# design.net
KiCad netlist of a schematic drawn in Altium Designer
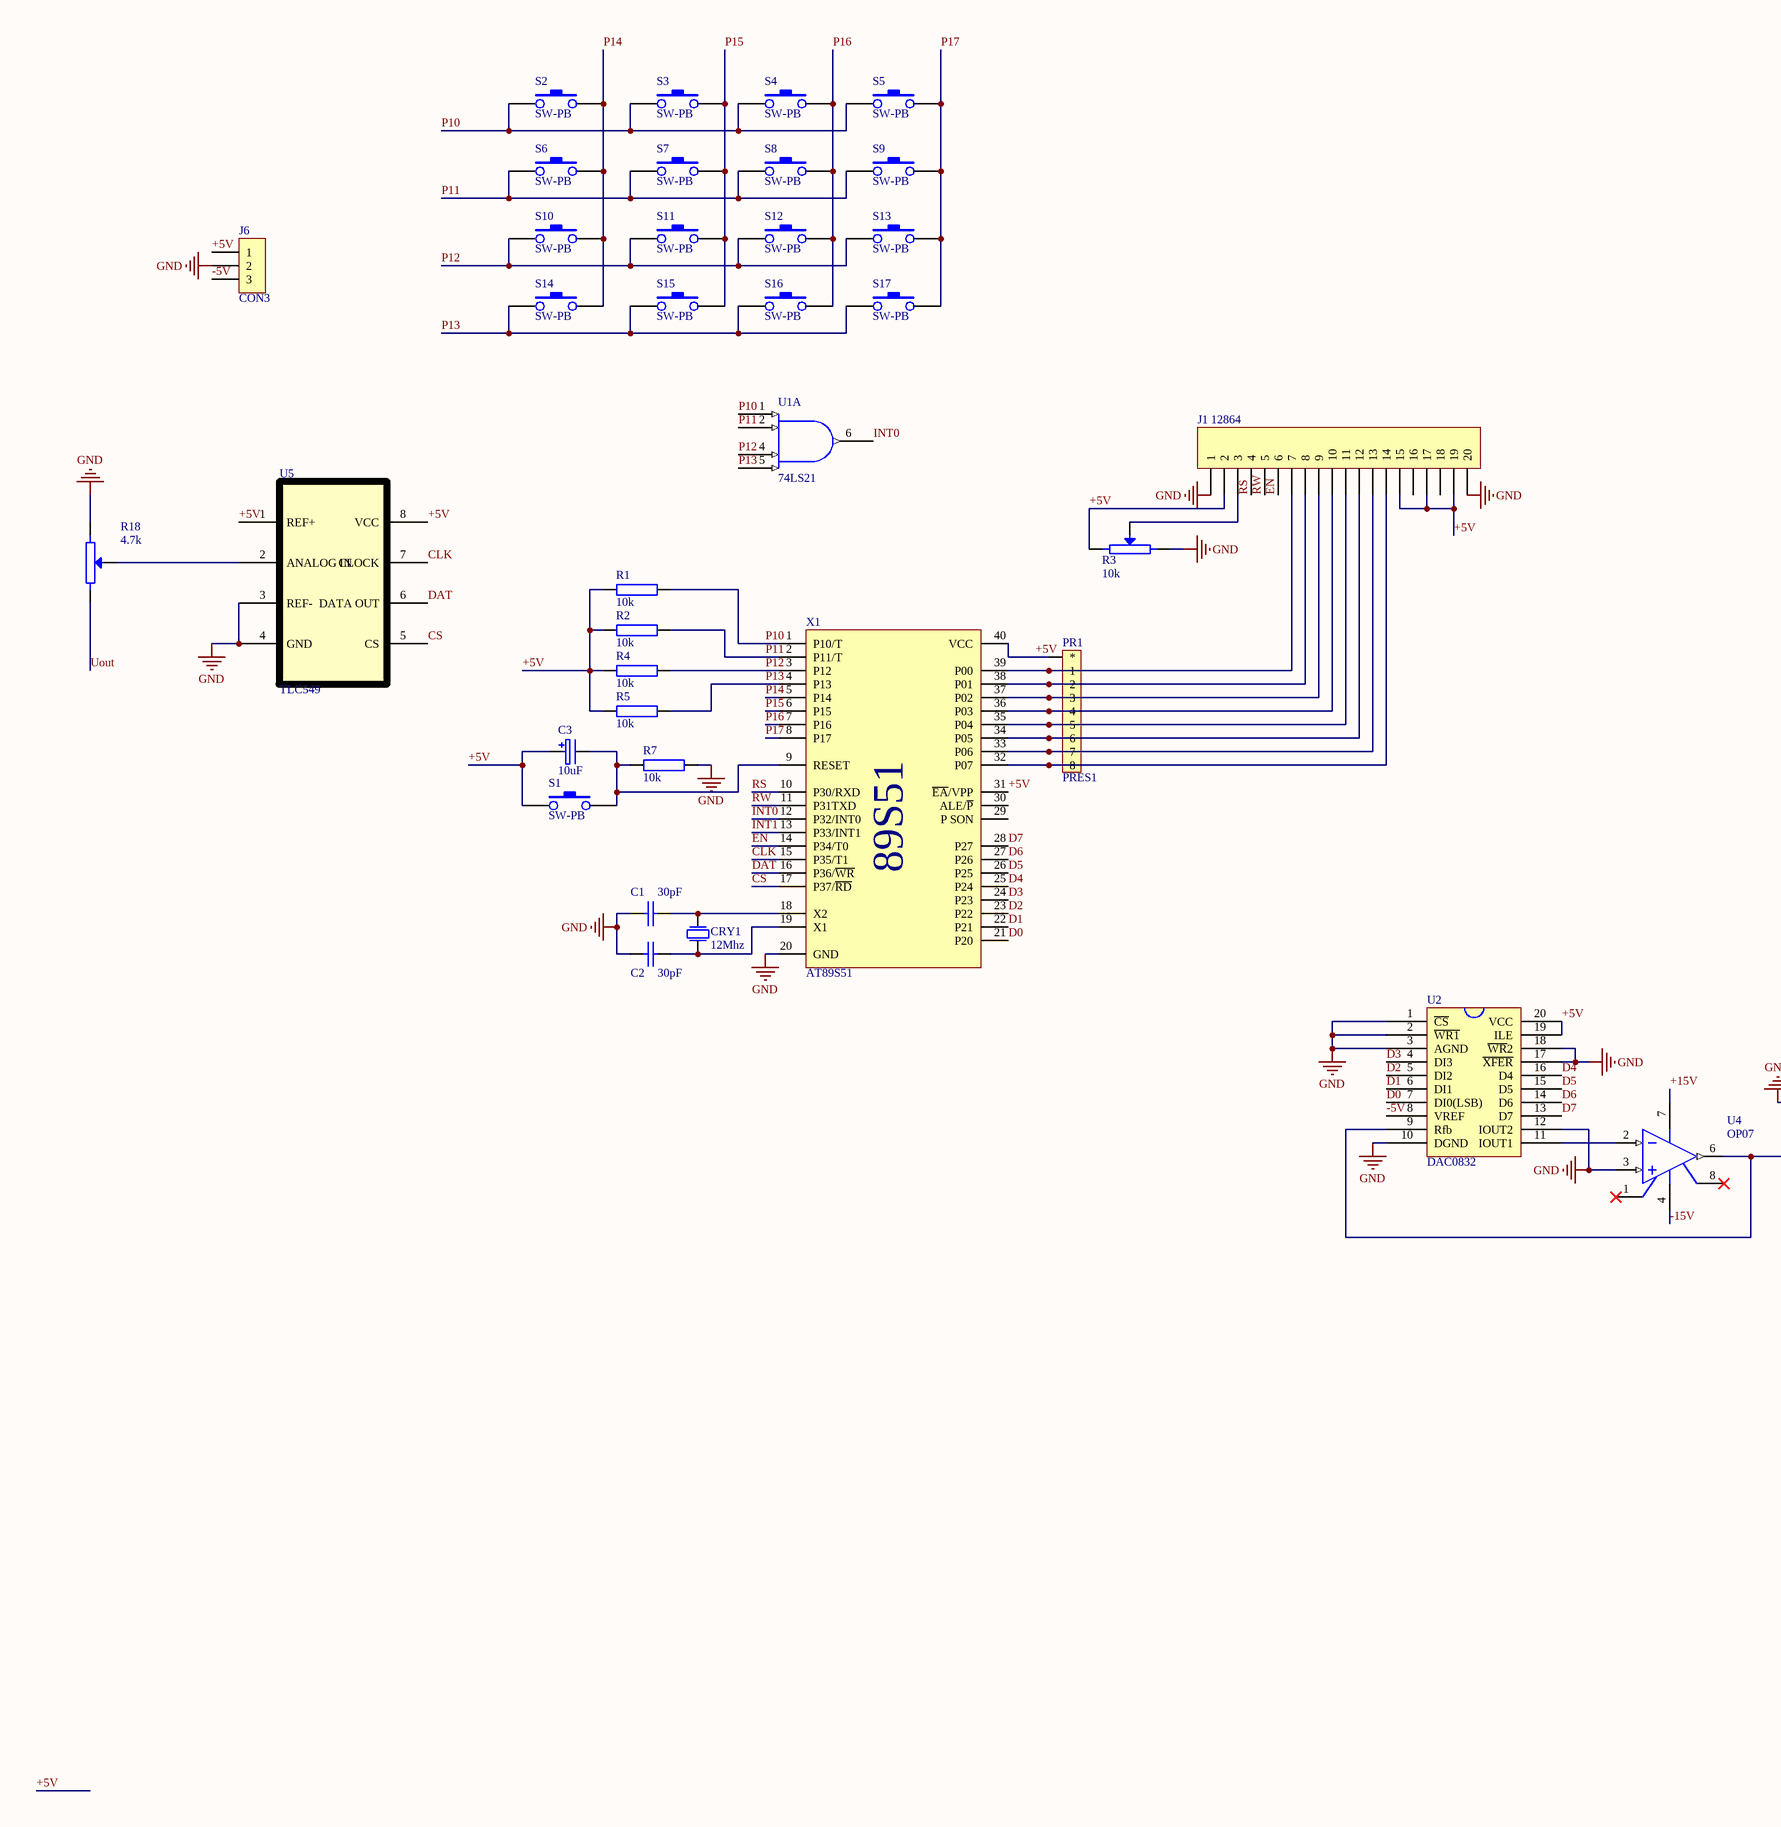
[diagram p0: 数控稳压电源.SchDoc, left]
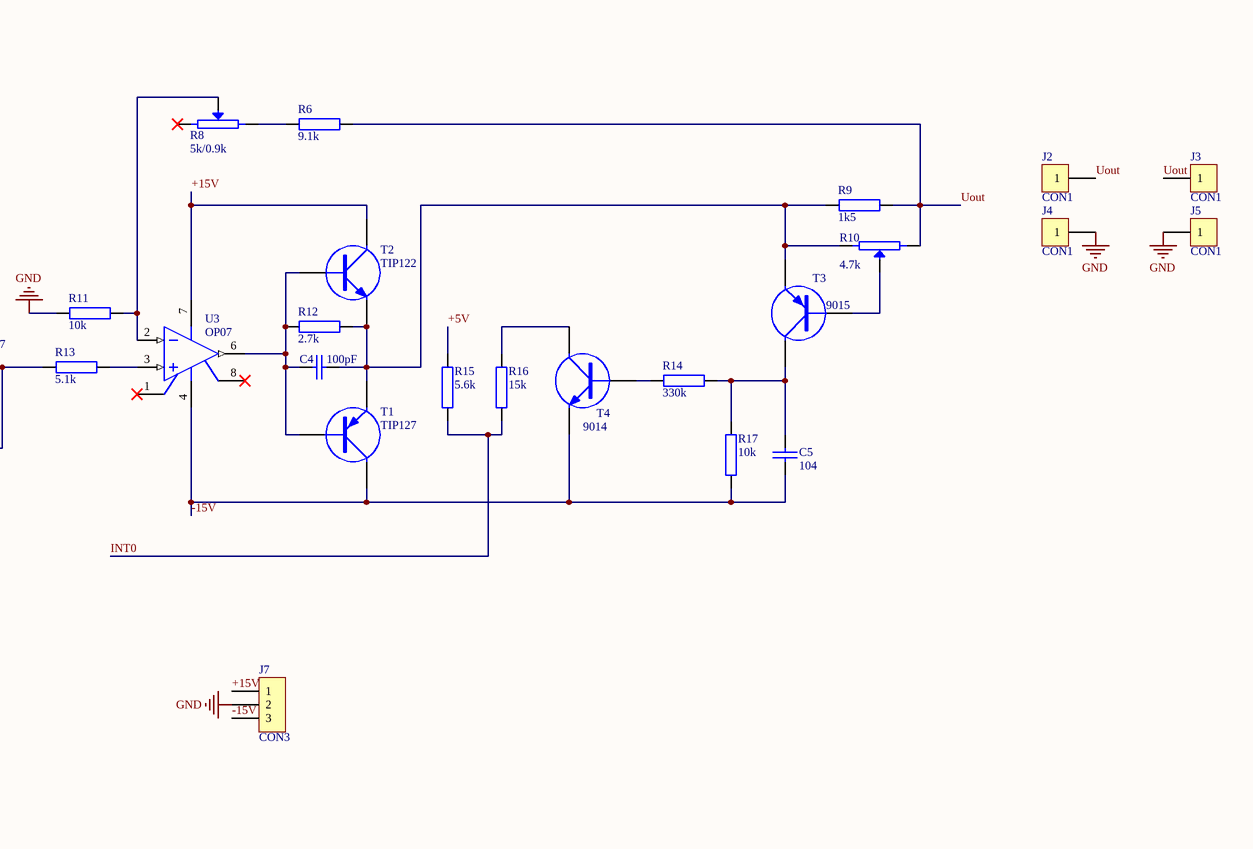
[diagram p1: 数控稳压电源.SchDoc, right]

(export (version "E")
  (design (tool "Eeschema 10.0.6"))
  (components
    (comp (ref "C1") (value "30pF") (footprint "CAP1") (libsource (lib "C电容") (part "CAP1")))
    (comp (ref "C2") (value "30pF") (footprint "CAP1") (libsource (lib "C电容") (part "CAP1")))
    (comp (ref "C3") (value "10uF") (footprint "RB1") (libsource (lib "C电容") (part "CAP3")))
    (comp (ref "C4") (value "100pF") (footprint "CAP1") (libsource (lib "C电容") (part "CAP1")))
    (comp (ref "C5") (value "104") (footprint "CAP1") (libsource (lib "C电容") (part "CAP1")))
    (comp (ref "CRY1")
      (value "12Mhz")
      (footprint "JZ1")
      (description "6.0000 8.000  11.0592  12.0000 24.000")
      (libsource (lib "J晶振") (part "CRY1"))
    )
    (comp (ref "J1")
      (value "12864")
      (footprint "sip20")
      (description "Connector")
      (libsource (lib "接口") (part "CON20"))
    )
    (comp (ref "J2")
      (value "CON1")
      (footprint "SIP-1")
      (description "Connector")
      (libsource (lib "") (part "CON1_1"))
    )
    (comp (ref "J3")
      (value "CON1")
      (footprint "SIP-1")
      (description "Connector")
      (libsource (lib "接口") (part "CON1"))
    )
    (comp (ref "J4")
      (value "CON1")
      (footprint "SIP-1")
      (description "Connector")
      (libsource (lib "") (part "CON1_1"))
    )
    (comp (ref "J5")
      (value "CON1")
      (footprint "SIP-1")
      (description "Connector")
      (libsource (lib "接口") (part "CON1"))
    )
    (comp (ref "J6")
      (value "CON3")
      (footprint "sip-3")
      (description "Connector")
      (libsource (lib "接口") (part "CON3"))
    )
    (comp (ref "J7")
      (value "CON3")
      (footprint "sip-3")
      (description "Connector")
      (libsource (lib "接口") (part "CON3"))
    )
    (comp (ref "PR1") (value "PRES1") (footprint "RP1") (libsource (lib "Resistance电阻") (part "PRES1")))
    (comp (ref "R1") (value "10k") (footprint "AXIAL0.3") (libsource (lib "电阻") (part "RES")))
    (comp (ref "R2") (value "10k") (footprint "AXIAL0.3") (libsource (lib "电阻") (part "RES")))
    (comp (ref "R3")
      (value "10k")
      (footprint "RVR-5")
      (description "Potentiometer")
      (libsource (lib "电阻") (part "RPOT2"))
    )
    (comp (ref "R4") (value "10k") (footprint "AXIAL0.3") (libsource (lib "电阻") (part "RES")))
    (comp (ref "R5") (value "10k") (footprint "AXIAL0.3") (libsource (lib "电阻") (part "RES")))
    (comp (ref "R6") (value "9.1k") (footprint "AXIAL0.3") (libsource (lib "电阻") (part "RES")))
    (comp (ref "R7") (value "10k") (footprint "AXIAL0.3") (libsource (lib "电阻") (part "RES")))
    (comp (ref "R8")
      (value "5k/0.9k")
      (footprint "VR5")
      (description "Potentiometer")
      (libsource (lib "电阻") (part "RPOT2"))
    )
    (comp (ref "R9") (value "1k5") (footprint "AXIAL0.3") (libsource (lib "电阻") (part "RES")))
    (comp (ref "R10")
      (value "4.7k")
      (footprint "VR5")
      (description "Potentiometer")
      (libsource (lib "电阻") (part "RPOT2"))
    )
    (comp (ref "R11") (value "10k") (footprint "AXIAL0.3") (libsource (lib "电阻") (part "RES")))
    (comp (ref "R12") (value "2.7k") (footprint "AXIAL0.3") (libsource (lib "电阻") (part "RES")))
    (comp (ref "R13") (value "5.1k") (footprint "AXIAL0.3") (libsource (lib "电阻") (part "RES")))
    (comp (ref "R14") (value "330k") (footprint "AXIAL0.3") (libsource (lib "电阻") (part "RES")))
    (comp (ref "R15") (value "5.6k") (footprint "AXIAL0.3") (libsource (lib "电阻") (part "RES")))
    (comp (ref "R16") (value "15k") (footprint "AXIAL0.3") (libsource (lib "电阻") (part "RES")))
    (comp (ref "R17") (value "10k") (footprint "AXIAL0.3") (libsource (lib "电阻") (part "RES")))
    (comp (ref "R18")
      (value "4.7k")
      (footprint "VR5")
      (description "Potentiometer")
      (libsource (lib "电阻") (part "RPOT2"))
    )
    (comp (ref "S1") (value "SW-PB") (footprint "SW6*6") (libsource (lib "SW开关") (part "SW-PB")))
    (comp (ref "S2") (value "SW-PB") (footprint "SW6*6") (libsource (lib "SW开关") (part "SW-PB")))
    (comp (ref "S3") (value "SW-PB") (footprint "SW6*6") (libsource (lib "SW开关") (part "SW-PB")))
    (comp (ref "S4") (value "SW-PB") (footprint "SW6*6") (libsource (lib "SW开关") (part "SW-PB")))
    (comp (ref "S5") (value "SW-PB") (footprint "SW6*6") (libsource (lib "SW开关") (part "SW-PB")))
    (comp (ref "S6") (value "SW-PB") (footprint "SW6*6") (libsource (lib "SW开关") (part "SW-PB")))
    (comp (ref "S7") (value "SW-PB") (footprint "SW6*6") (libsource (lib "SW开关") (part "SW-PB")))
    (comp (ref "S8") (value "SW-PB") (footprint "SW6*6") (libsource (lib "SW开关") (part "SW-PB")))
    (comp (ref "S9") (value "SW-PB") (footprint "SW6*6") (libsource (lib "SW开关") (part "SW-PB")))
    (comp (ref "S10") (value "SW-PB") (footprint "SW6*6") (libsource (lib "SW开关") (part "SW-PB")))
    (comp (ref "S11") (value "SW-PB") (footprint "SW6*6") (libsource (lib "SW开关") (part "SW-PB")))
    (comp (ref "S12") (value "SW-PB") (footprint "SW6*6") (libsource (lib "SW开关") (part "SW-PB")))
    (comp (ref "S13") (value "SW-PB") (footprint "SW6*6") (libsource (lib "SW开关") (part "SW-PB")))
    (comp (ref "S14") (value "SW-PB") (footprint "SW6*6") (libsource (lib "SW开关") (part "SW-PB")))
    (comp (ref "S15") (value "SW-PB") (footprint "SW6*6") (libsource (lib "SW开关") (part "SW-PB")))
    (comp (ref "S16") (value "SW-PB") (footprint "SW6*6") (libsource (lib "SW开关") (part "SW-PB")))
    (comp (ref "S17") (value "SW-PB") (footprint "SW6*6") (libsource (lib "SW开关") (part "SW-PB")))
    (comp (ref "T1")
      (value "TIP127")
      (footprint "TO220B")
      (description "PNP PLASTIC POWER TRANSISTORS")
      (libsource (lib "Transistor三极管") (part "TIP42"))
    )
    (comp (ref "T2")
      (value "TIP122")
      (footprint "TO220B")
      (description "NPN PLASTIC POWER TRANSISTORS")
      (libsource (lib "Transistor三极管") (part "TIP41"))
    )
    (comp (ref "T3")
      (value "9015")
      (footprint "TO-92")
      (description "低电平、低噪的前置放大器做放大或震荡")
      (libsource (lib "Transistor三极管") (part "9015"))
    )
    (comp (ref "T4")
      (value "9014")
      (footprint "TO-92")
      (description "低电平、低噪的前置放大器做放大或震荡")
      (libsource (lib "Transistor三极管") (part "9014"))
    )
    (comp (ref "U1") (value "74LS21") (footprint "DIP-14") (libsource (lib "74xxTTL") (part "74LS21")))
    (comp (ref "U2") (value "DAC0832") (footprint "DIP-20") (libsource (lib "集成块") (part "DAC0832")))
    (comp (ref "U3")
      (value "OP07")
      (footprint "DIP-8")
      (description "Precision Operational Amplifier")
      (libsource (lib "OpAmp比较器") (part "OP07"))
    )
    (comp (ref "U4")
      (value "OP07")
      (footprint "DIP-8")
      (description "Precision Operational Amplifier")
      (libsource (lib "OpAmp比较器") (part "OP07"))
    )
    (comp (ref "U5") (value "TLC549") (footprint "DIP-8") (libsource (lib "TLC549") (part "TLC549")))
    (comp (ref "X1") (value "AT89S51") (footprint "DIP40") (libsource (lib "MCU微处理器") (part "AT89S51")))
  )
  (nets
    (net (code "1") (name "/+5V") (class "Default")
      (node (ref "C3") (pin "1") (pintype "passive"))
      (node (ref "J1") (pin "15") (pinfunction "15_15") (pintype "passive"))
      (node (ref "J1") (pin "17") (pinfunction "17_17") (pintype "passive"))
      (node (ref "J1") (pin "19") (pinfunction "19_19") (pintype "passive"))
      (node (ref "J1") (pin "2") (pinfunction "2_2") (pintype "passive"))
      (node (ref "J6") (pin "1") (pinfunction "1_1") (pintype "passive"))
      (node (ref "PR1") (pin "1") (pinfunction "*_1") (pintype "passive"))
      (node (ref "R1") (pin "1") (pinfunction "1_1") (pintype "passive"))
      (node (ref "R15") (pin "1") (pinfunction "1_1") (pintype "passive"))
      (node (ref "R2") (pin "1") (pinfunction "1_1") (pintype "passive"))
      (node (ref "R3") (pin "1") (pinfunction "1_1") (pintype "passive"))
      (node (ref "R4") (pin "1") (pinfunction "1_1") (pintype "passive"))
      (node (ref "R5") (pin "1") (pinfunction "1_1") (pintype "passive"))
      (node (ref "S1") (pin "1") (pinfunction "1_1") (pintype "passive"))
      (node (ref "U2") (pin "19") (pinfunction "ILE_19") (pintype "passive"))
      (node (ref "U2") (pin "20") (pinfunction "VCC_20") (pintype "passive"))
      (node (ref "U5") (pin "1") (pinfunction "REF+_1") (pintype "passive"))
      (node (ref "U5") (pin "8") (pinfunction "VCC_8") (pintype "passive"))
      (node (ref "X1") (pin "31") (pinfunction "~{EA}/VPP_31") (pintype "passive"))
      (node (ref "X1") (pin "40") (pinfunction "VCC_40") (pintype "passive"))
    )
    (net (code "2") (name "/+15V") (class "Default")
      (node (ref "J7") (pin "1") (pinfunction "1_1") (pintype "passive"))
      (node (ref "T2") (pin "2") (pinfunction "C_2") (pintype "passive"))
      (node (ref "U3") (pin "7") (pinfunction "V+_7") (pintype "power_in"))
      (node (ref "U4") (pin "7") (pinfunction "V+_7") (pintype "power_in"))
    )
    (net (code "3") (name "/-5V") (class "Default")
      (node (ref "J6") (pin "3") (pinfunction "3_3") (pintype "passive"))
      (node (ref "U2") (pin "8") (pinfunction "VREF_8") (pintype "passive"))
    )
    (net (code "4") (name "/-15V") (class "Default")
      (node (ref "C5") (pin "1") (pinfunction "1_1") (pintype "passive"))
      (node (ref "J7") (pin "3") (pinfunction "3_3") (pintype "passive"))
      (node (ref "R17") (pin "2") (pinfunction "2_2") (pintype "passive"))
      (node (ref "T1") (pin "2") (pinfunction "C_2") (pintype "passive"))
      (node (ref "T4") (pin "1") (pinfunction "E_1") (pintype "passive"))
      (node (ref "U3") (pin "4") (pinfunction "V-_4") (pintype "power_in"))
      (node (ref "U4") (pin "4") (pinfunction "V-_4") (pintype "power_in"))
    )
    (net (code "5") (name "/CLK") (class "Default")
      (node (ref "U5") (pin "7") (pinfunction "CLOCK_7") (pintype "passive"))
      (node (ref "X1") (pin "15") (pinfunction "P35/T1_15") (pintype "passive"))
    )
    (net (code "6") (name "/CS") (class "Default")
      (node (ref "U5") (pin "5") (pinfunction "CS_5") (pintype "passive"))
      (node (ref "X1") (pin "17") (pinfunction "P37/~{RD}_17") (pintype "passive"))
    )
    (net (code "7") (name "/D0") (class "Default")
      (node (ref "U2") (pin "7") (pinfunction "DI0(LSB)_7") (pintype "passive"))
      (node (ref "X1") (pin "21") (pinfunction "P20_21") (pintype "passive"))
    )
    (net (code "8") (name "/D1") (class "Default")
      (node (ref "U2") (pin "6") (pinfunction "DI1_6") (pintype "passive"))
      (node (ref "X1") (pin "22") (pinfunction "P21_22") (pintype "passive"))
    )
    (net (code "9") (name "/D2") (class "Default")
      (node (ref "U2") (pin "5") (pinfunction "DI2_5") (pintype "passive"))
      (node (ref "X1") (pin "23") (pinfunction "P22_23") (pintype "passive"))
    )
    (net (code "10") (name "/D3") (class "Default")
      (node (ref "U2") (pin "4") (pinfunction "DI3_4") (pintype "passive"))
      (node (ref "X1") (pin "24") (pinfunction "P23_24") (pintype "passive"))
    )
    (net (code "11") (name "/D4") (class "Default")
      (node (ref "U2") (pin "16") (pinfunction "D4_16") (pintype "passive"))
      (node (ref "X1") (pin "25") (pinfunction "P24_25") (pintype "passive"))
    )
    (net (code "12") (name "/D5") (class "Default")
      (node (ref "U2") (pin "15") (pinfunction "D5_15") (pintype "passive"))
      (node (ref "X1") (pin "26") (pinfunction "P25_26") (pintype "passive"))
    )
    (net (code "13") (name "/D6") (class "Default")
      (node (ref "U2") (pin "14") (pinfunction "D6_14") (pintype "passive"))
      (node (ref "X1") (pin "27") (pinfunction "P26_27") (pintype "passive"))
    )
    (net (code "14") (name "/D7") (class "Default")
      (node (ref "U2") (pin "13") (pinfunction "D7_13") (pintype "passive"))
      (node (ref "X1") (pin "28") (pinfunction "P27_28") (pintype "passive"))
    )
    (net (code "15") (name "/DAT") (class "Default")
      (node (ref "U5") (pin "6") (pinfunction "DATA_OUT_6") (pintype "passive"))
      (node (ref "X1") (pin "16") (pinfunction "P36/~{WR}_16") (pintype "passive"))
    )
    (net (code "16") (name "/EN") (class "Default")
      (node (ref "J1") (pin "6") (pinfunction "6_6") (pintype "passive"))
      (node (ref "X1") (pin "14") (pinfunction "P34/T0_14") (pintype "passive"))
    )
    (net (code "17") (name "/INT0") (class "Default")
      (node (ref "R15") (pin "2") (pinfunction "2_2") (pintype "passive"))
      (node (ref "R16") (pin "2") (pinfunction "2_2") (pintype "passive"))
      (node (ref "U1") (pin "6") (pintype "output"))
      (node (ref "X1") (pin "12") (pinfunction "P32/INT0_12") (pintype "passive"))
    )
    (net (code "18") (name "/INT1") (class "Default")
      (node (ref "X1") (pin "13") (pinfunction "P33/INT1_13") (pintype "passive"))
    )
    (net (code "19") (name "/P10") (class "Default")
      (node (ref "R1") (pin "2") (pinfunction "2_2") (pintype "passive"))
      (node (ref "S2") (pin "1") (pinfunction "1_1") (pintype "passive"))
      (node (ref "S3") (pin "1") (pinfunction "1_1") (pintype "passive"))
      (node (ref "S4") (pin "1") (pinfunction "1_1") (pintype "passive"))
      (node (ref "S5") (pin "1") (pinfunction "1_1") (pintype "passive"))
      (node (ref "U1") (pin "1") (pintype "input"))
      (node (ref "X1") (pin "1") (pinfunction "P10/T_1") (pintype "passive"))
    )
    (net (code "20") (name "/P11") (class "Default")
      (node (ref "R2") (pin "2") (pinfunction "2_2") (pintype "passive"))
      (node (ref "S6") (pin "1") (pinfunction "1_1") (pintype "passive"))
      (node (ref "S7") (pin "1") (pinfunction "1_1") (pintype "passive"))
      (node (ref "S8") (pin "1") (pinfunction "1_1") (pintype "passive"))
      (node (ref "S9") (pin "1") (pinfunction "1_1") (pintype "passive"))
      (node (ref "U1") (pin "2") (pintype "input"))
      (node (ref "X1") (pin "2") (pinfunction "P11/T_2") (pintype "passive"))
    )
    (net (code "21") (name "/P12") (class "Default")
      (node (ref "R4") (pin "2") (pinfunction "2_2") (pintype "passive"))
      (node (ref "S10") (pin "1") (pinfunction "1_1") (pintype "passive"))
      (node (ref "S11") (pin "1") (pinfunction "1_1") (pintype "passive"))
      (node (ref "S12") (pin "1") (pinfunction "1_1") (pintype "passive"))
      (node (ref "S13") (pin "1") (pinfunction "1_1") (pintype "passive"))
      (node (ref "U1") (pin "4") (pintype "input"))
      (node (ref "X1") (pin "3") (pinfunction "P12_3") (pintype "passive"))
    )
    (net (code "22") (name "/P13") (class "Default")
      (node (ref "R5") (pin "2") (pinfunction "2_2") (pintype "passive"))
      (node (ref "S14") (pin "1") (pinfunction "1_1") (pintype "passive"))
      (node (ref "S15") (pin "1") (pinfunction "1_1") (pintype "passive"))
      (node (ref "S16") (pin "1") (pinfunction "1_1") (pintype "passive"))
      (node (ref "S17") (pin "1") (pinfunction "1_1") (pintype "passive"))
      (node (ref "U1") (pin "5") (pintype "input"))
      (node (ref "X1") (pin "4") (pinfunction "P13_4") (pintype "passive"))
    )
    (net (code "23") (name "/P14") (class "Default")
      (node (ref "S10") (pin "2") (pinfunction "2_2") (pintype "passive"))
      (node (ref "S14") (pin "2") (pinfunction "2_2") (pintype "passive"))
      (node (ref "S2") (pin "2") (pinfunction "2_2") (pintype "passive"))
      (node (ref "S6") (pin "2") (pinfunction "2_2") (pintype "passive"))
      (node (ref "X1") (pin "5") (pinfunction "P14_5") (pintype "passive"))
    )
    (net (code "24") (name "/P15") (class "Default")
      (node (ref "S11") (pin "2") (pinfunction "2_2") (pintype "passive"))
      (node (ref "S15") (pin "2") (pinfunction "2_2") (pintype "passive"))
      (node (ref "S3") (pin "2") (pinfunction "2_2") (pintype "passive"))
      (node (ref "S7") (pin "2") (pinfunction "2_2") (pintype "passive"))
      (node (ref "X1") (pin "6") (pinfunction "P15_6") (pintype "passive"))
    )
    (net (code "25") (name "/P16") (class "Default")
      (node (ref "S12") (pin "2") (pinfunction "2_2") (pintype "passive"))
      (node (ref "S16") (pin "2") (pinfunction "2_2") (pintype "passive"))
      (node (ref "S4") (pin "2") (pinfunction "2_2") (pintype "passive"))
      (node (ref "S8") (pin "2") (pinfunction "2_2") (pintype "passive"))
      (node (ref "X1") (pin "7") (pinfunction "P16_7") (pintype "passive"))
    )
    (net (code "26") (name "/P17") (class "Default")
      (node (ref "S13") (pin "2") (pinfunction "2_2") (pintype "passive"))
      (node (ref "S17") (pin "2") (pinfunction "2_2") (pintype "passive"))
      (node (ref "S5") (pin "2") (pinfunction "2_2") (pintype "passive"))
      (node (ref "S9") (pin "2") (pinfunction "2_2") (pintype "passive"))
      (node (ref "X1") (pin "8") (pinfunction "P17_8") (pintype "passive"))
    )
    (net (code "27") (name "/RS") (class "Default")
      (node (ref "J1") (pin "4") (pinfunction "4_4") (pintype "passive"))
      (node (ref "X1") (pin "10") (pinfunction "P30/RXD_10") (pintype "passive"))
    )
    (net (code "28") (name "/RW") (class "Default")
      (node (ref "J1") (pin "5") (pinfunction "5_5") (pintype "passive"))
      (node (ref "X1") (pin "11") (pinfunction "P31TXD_11") (pintype "passive"))
    )
    (net (code "29") (name "/Uout") (class "Default")
      (node (ref "J2") (pin "1") (pinfunction "1_1") (pintype "passive"))
      (node (ref "J3") (pin "1") (pinfunction "1_1") (pintype "passive"))
      (node (ref "R10") (pin "1") (pinfunction "1_1") (pintype "passive"))
      (node (ref "R18") (pin "3") (pinfunction "2_3") (pintype "passive"))
      (node (ref "R6") (pin "1") (pinfunction "1_1") (pintype "passive"))
      (node (ref "R9") (pin "2") (pinfunction "2_2") (pintype "passive"))
    )
    (net (code "30") (name "GND") (class "Default")
      (node (ref "C1") (pin "1") (pinfunction "1_1") (pintype "passive"))
      (node (ref "C2") (pin "1") (pinfunction "1_1") (pintype "passive"))
      (node (ref "J1") (pin "1") (pinfunction "1_1") (pintype "passive"))
      (node (ref "J1") (pin "20") (pinfunction "20_20") (pintype "passive"))
      (node (ref "J4") (pin "1") (pinfunction "1_1") (pintype "passive"))
      (node (ref "J5") (pin "1") (pinfunction "1_1") (pintype "passive"))
      (node (ref "J6") (pin "2") (pinfunction "2_2") (pintype "passive"))
      (node (ref "J7") (pin "2") (pinfunction "2_2") (pintype "passive"))
      (node (ref "R11") (pin "2") (pinfunction "2_2") (pintype "passive"))
      (node (ref "R18") (pin "1") (pinfunction "1_1") (pintype "passive"))
      (node (ref "R3") (pin "3") (pinfunction "2_3") (pintype "passive"))
      (node (ref "R7") (pin "2") (pinfunction "2_2") (pintype "passive"))
      (node (ref "U1") (pin "7") (pinfunction "GND_7") (pintype "power_in"))
      (node (ref "U2") (pin "1") (pinfunction "~{CS}_1") (pintype "passive"))
      (node (ref "U2") (pin "10") (pinfunction "DGND_10") (pintype "passive"))
      (node (ref "U2") (pin "12") (pinfunction "IOUT2_12") (pintype "passive"))
      (node (ref "U2") (pin "17") (pinfunction "~{XFER}_17") (pintype "passive"))
      (node (ref "U2") (pin "18") (pinfunction "~{WR}2_18") (pintype "passive"))
      (node (ref "U2") (pin "2") (pinfunction "~{WR1}_2") (pintype "passive"))
      (node (ref "U2") (pin "3") (pinfunction "AGND_3") (pintype "passive"))
      (node (ref "U4") (pin "3") (pinfunction "+IN_3") (pintype "input"))
      (node (ref "U5") (pin "3") (pinfunction "REF-_3") (pintype "passive"))
      (node (ref "U5") (pin "4") (pinfunction "GND_4") (pintype "passive"))
      (node (ref "X1") (pin "20") (pinfunction "GND_20") (pintype "passive"))
    )
    (net (code "31") (name "Net-(CRY1-P1)") (class "Default")
      (node (ref "C1") (pin "2") (pinfunction "2_2") (pintype "passive"))
      (node (ref "CRY1") (pin "1") (pinfunction "P1_1") (pintype "passive"))
      (node (ref "X1") (pin "18") (pinfunction "X2_18") (pintype "passive"))
    )
    (net (code "32") (name "Net-(CRY1-P2)") (class "Default")
      (node (ref "C2") (pin "2") (pinfunction "2_2") (pintype "passive"))
      (node (ref "CRY1") (pin "2") (pinfunction "P2_2") (pintype "passive"))
      (node (ref "X1") (pin "19") (pinfunction "X1_19") (pintype "passive"))
    )
    (net (code "33") (name "Net-(PR1-1)") (class "Default")
      (node (ref "J1") (pin "7") (pinfunction "7_7") (pintype "passive"))
      (node (ref "PR1") (pin "2") (pinfunction "1_2") (pintype "passive"))
      (node (ref "X1") (pin "39") (pinfunction "P00_39") (pintype "passive"))
    )
    (net (code "34") (name "Net-(PR1-2)") (class "Default")
      (node (ref "J1") (pin "8") (pinfunction "8_8") (pintype "passive"))
      (node (ref "PR1") (pin "3") (pinfunction "2_3") (pintype "passive"))
      (node (ref "X1") (pin "38") (pinfunction "P01_38") (pintype "passive"))
    )
    (net (code "35") (name "Net-(PR1-3)") (class "Default")
      (node (ref "J1") (pin "9") (pinfunction "9_9") (pintype "passive"))
      (node (ref "PR1") (pin "4") (pinfunction "3_4") (pintype "passive"))
      (node (ref "X1") (pin "37") (pinfunction "P02_37") (pintype "passive"))
    )
    (net (code "36") (name "Net-(PR1-4)") (class "Default")
      (node (ref "J1") (pin "10") (pinfunction "10_10") (pintype "passive"))
      (node (ref "PR1") (pin "5") (pinfunction "4_5") (pintype "passive"))
      (node (ref "X1") (pin "36") (pinfunction "P03_36") (pintype "passive"))
    )
    (net (code "37") (name "Net-(PR1-5)") (class "Default")
      (node (ref "J1") (pin "11") (pinfunction "11_11") (pintype "passive"))
      (node (ref "PR1") (pin "6") (pinfunction "5_6") (pintype "passive"))
      (node (ref "X1") (pin "35") (pinfunction "P04_35") (pintype "passive"))
    )
    (net (code "38") (name "Net-(PR1-6)") (class "Default")
      (node (ref "J1") (pin "12") (pinfunction "12_12") (pintype "passive"))
      (node (ref "PR1") (pin "7") (pinfunction "6_7") (pintype "passive"))
      (node (ref "X1") (pin "34") (pinfunction "P05_34") (pintype "passive"))
    )
    (net (code "39") (name "Net-(PR1-7)") (class "Default")
      (node (ref "J1") (pin "13") (pinfunction "13_13") (pintype "passive"))
      (node (ref "PR1") (pin "8") (pinfunction "7_8") (pintype "passive"))
      (node (ref "X1") (pin "33") (pinfunction "P06_33") (pintype "passive"))
    )
    (net (code "40") (name "Net-(PR1-8)") (class "Default")
      (node (ref "J1") (pin "14") (pinfunction "14_14") (pintype "passive"))
      (node (ref "PR1") (pin "9") (pinfunction "8_9") (pintype "passive"))
      (node (ref "X1") (pin "32") (pinfunction "P07_32") (pintype "passive"))
    )
    (net (code "41") (name "Net-(R3-VT)") (class "Default")
      (node (ref "J1") (pin "3") (pinfunction "3_3") (pintype "passive"))
      (node (ref "R3") (pin "2") (pinfunction "VT_2") (pintype "passive"))
    )
    (net (code "42") (name "Net-(R8-2)") (class "Default")
      (node (ref "R6") (pin "2") (pinfunction "2_2") (pintype "passive"))
      (node (ref "R8") (pin "3") (pinfunction "2_3") (pintype "passive"))
    )
    (net (code "43") (name "Net-(R8-VT)") (class "Default")
      (node (ref "R11") (pin "1") (pinfunction "1_1") (pintype "passive"))
      (node (ref "R8") (pin "2") (pinfunction "VT_2") (pintype "passive"))
      (node (ref "U3") (pin "2") (pinfunction "-IN_2") (pintype "input"))
    )
    (net (code "44") (name "Net-(R10-2)") (class "Default")
      (node (ref "C4") (pin "2") (pinfunction "2_2") (pintype "passive"))
      (node (ref "R10") (pin "3") (pinfunction "2_3") (pintype "passive"))
      (node (ref "R12") (pin "1") (pinfunction "1_1") (pintype "passive"))
      (node (ref "R9") (pin "1") (pinfunction "1_1") (pintype "passive"))
      (node (ref "T1") (pin "3") (pinfunction "E_3") (pintype "passive"))
      (node (ref "T2") (pin "3") (pinfunction "E_3") (pintype "passive"))
      (node (ref "T3") (pin "1") (pinfunction "E_1") (pintype "passive"))
    )
    (net (code "45") (name "Net-(R10-VT)") (class "Default")
      (node (ref "R10") (pin "2") (pinfunction "VT_2") (pintype "passive"))
      (node (ref "T3") (pin "2") (pinfunction "B_2") (pintype "passive"))
    )
    (net (code "46") (name "Net-(R18-VT)") (class "Default")
      (node (ref "R18") (pin "2") (pinfunction "VT_2") (pintype "passive"))
      (node (ref "U5") (pin "2") (pinfunction "ANALOG_IN_2") (pintype "passive"))
    )
    (net (code "47") (name "Net-(T1-B)") (class "Default")
      (node (ref "C4") (pin "1") (pinfunction "1_1") (pintype "passive"))
      (node (ref "R12") (pin "2") (pinfunction "2_2") (pintype "passive"))
      (node (ref "T1") (pin "1") (pinfunction "B_1") (pintype "passive"))
      (node (ref "T2") (pin "1") (pinfunction "B_1") (pintype "passive"))
      (node (ref "U3") (pin "6") (pinfunction "OUT_6") (pintype "output"))
    )
    (net (code "48") (name "Net-(T3-C)") (class "Default")
      (node (ref "C5") (pin "2") (pinfunction "2_2") (pintype "passive"))
      (node (ref "R14") (pin "2") (pinfunction "2_2") (pintype "passive"))
      (node (ref "R17") (pin "1") (pinfunction "1_1") (pintype "passive"))
      (node (ref "T3") (pin "3") (pinfunction "C_3") (pintype "passive"))
    )
    (net (code "49") (name "Net-(T4-B)") (class "Default")
      (node (ref "R14") (pin "1") (pinfunction "1_1") (pintype "passive"))
      (node (ref "T4") (pin "2") (pinfunction "B_2") (pintype "passive"))
    )
    (net (code "50") (name "Net-(T4-C)") (class "Default")
      (node (ref "R16") (pin "1") (pinfunction "1_1") (pintype "passive"))
      (node (ref "T4") (pin "3") (pinfunction "C_3") (pintype "passive"))
    )
    (net (code "51") (name "Net-(U2-IOUT1)") (class "Default")
      (node (ref "U2") (pin "11") (pinfunction "IOUT1_11") (pintype "passive"))
      (node (ref "U4") (pin "2") (pinfunction "-IN_2") (pintype "input"))
    )
    (net (code "52") (name "Net-(U2-Rfb)") (class "Default")
      (node (ref "R13") (pin "1") (pinfunction "1_1") (pintype "passive"))
      (node (ref "U2") (pin "9") (pinfunction "Rfb_9") (pintype "passive"))
      (node (ref "U4") (pin "6") (pinfunction "OUT_6") (pintype "output"))
    )
    (net (code "53") (name "Net-(U3-+IN)") (class "Default")
      (node (ref "R13") (pin "2") (pinfunction "2_2") (pintype "passive"))
      (node (ref "U3") (pin "3") (pinfunction "+IN_3") (pintype "input"))
    )
    (net (code "54") (name "Net-(X1-RESET)") (class "Default")
      (node (ref "C3") (pin "2") (pintype "passive"))
      (node (ref "R7") (pin "1") (pinfunction "1_1") (pintype "passive"))
      (node (ref "S1") (pin "2") (pinfunction "2_2") (pintype "passive"))
      (node (ref "X1") (pin "9") (pinfunction "RESET_9") (pintype "passive"))
    )
    (net (code "55") (name "VCC") (class "Default")
      (node (ref "U1") (pin "14") (pinfunction "VCC_14") (pintype "power_in"))
    )
    (net (code "56") (name "unconnected-(J1-Pad16)") (class "Default")
      (node (ref "J1") (pin "16") (pinfunction "16_16") (pintype "passive"))
    )
    (net (code "57") (name "unconnected-(J1-Pad18)") (class "Default")
      (node (ref "J1") (pin "18") (pinfunction "18_18") (pintype "passive"))
    )
    (net (code "58") (name "unconnected-(R8-Pad1)") (class "Default")
      (node (ref "R8") (pin "1") (pinfunction "1_1") (pintype "passive+no_connect"))
    )
    (net (code "59") (name "unconnected-(U3-TRIM-Pad1)") (class "Default")
      (node (ref "U3") (pin "1") (pinfunction "TRIM_1") (pintype "passive+no_connect"))
    )
    (net (code "60") (name "unconnected-(U3-TRIM-Pad8)") (class "Default")
      (node (ref "U3") (pin "8") (pinfunction "TRIM_8") (pintype "passive+no_connect"))
    )
    (net (code "61") (name "unconnected-(U4-TRIM-Pad1)") (class "Default")
      (node (ref "U4") (pin "1") (pinfunction "TRIM_1") (pintype "passive+no_connect"))
    )
    (net (code "62") (name "unconnected-(U4-TRIM-Pad8)") (class "Default")
      (node (ref "U4") (pin "8") (pinfunction "TRIM_8") (pintype "passive+no_connect"))
    )
    (net (code "63") (name "unconnected-(X1-ALE{slash}~{P}-Pad30)") (class "Default")
      (node (ref "X1") (pin "30") (pinfunction "ALE/~{P}_30") (pintype "passive"))
    )
    (net (code "64") (name "unconnected-(X1-P_SON-Pad29)") (class "Default")
      (node (ref "X1") (pin "29") (pinfunction "P_SON_29") (pintype "passive"))
    )
  )
)
